# Nebula_1_7OLED.net
KiCad netlist of a schematic drawn in Altium Designer
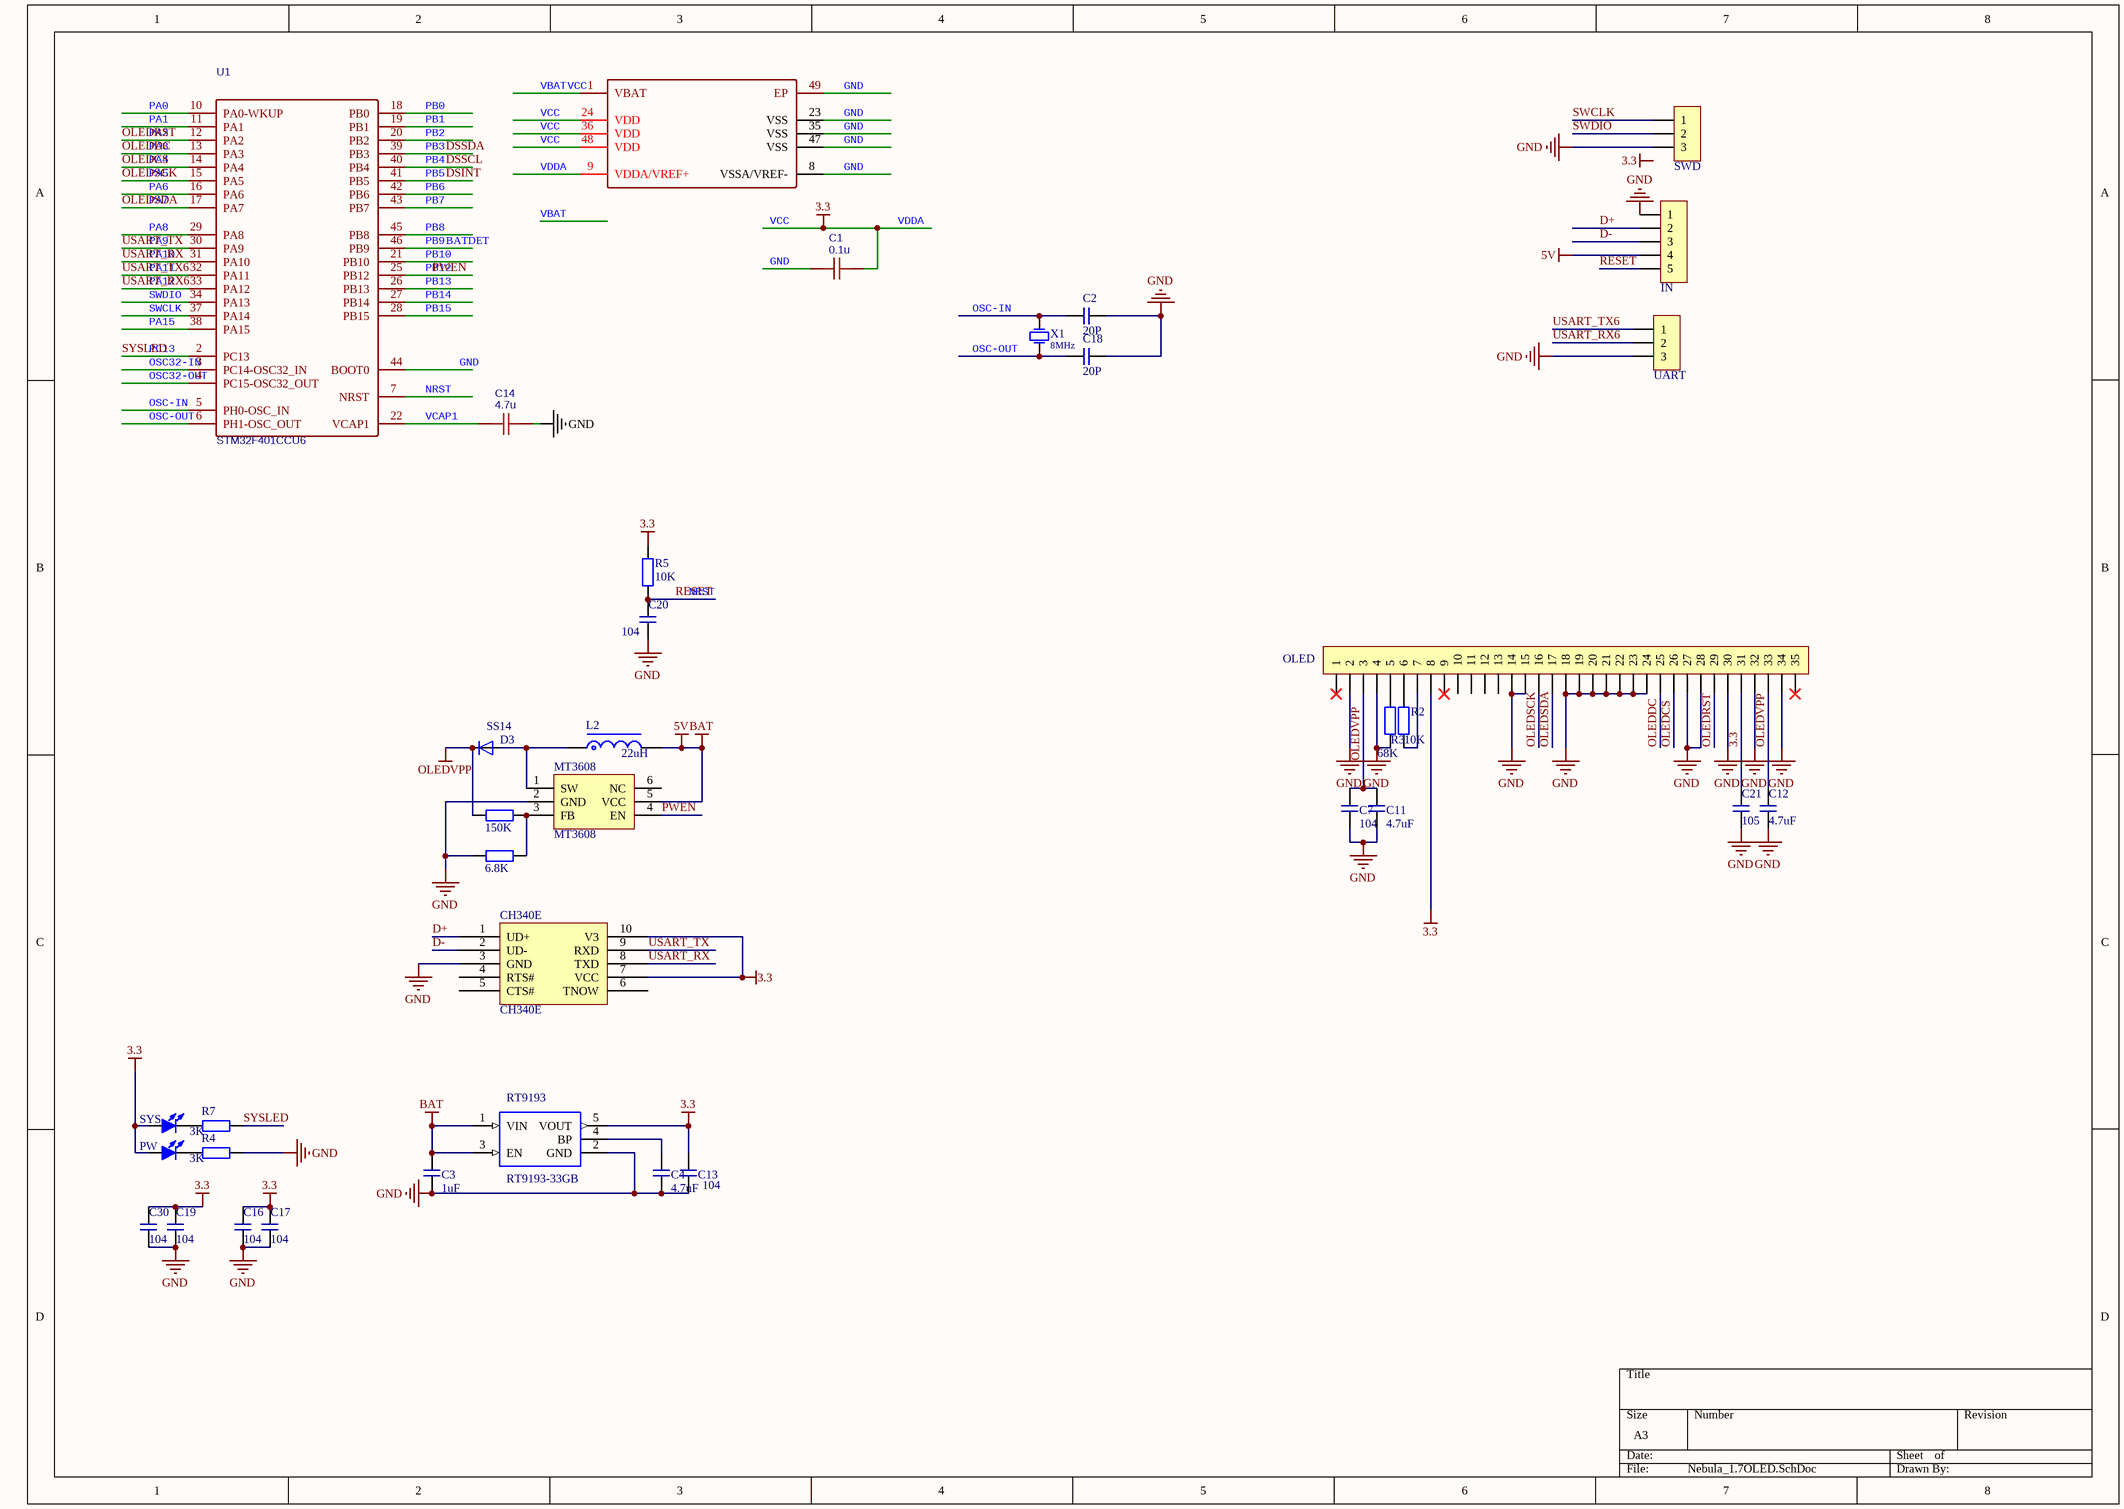
[diagram p0: Nebula_1.7OLED.SchDoc]

(export (version "E")
  (design (tool "Eeschema 10.0.6"))
  (components
    (comp (ref "C1")
      (value "0.1u")
      (footprint "0603C")
      (fields (field (name "CONTRIBUTOR") "LCEDA_Lib"))
      (libsource (lib "altium-import") (part "root_2_0.1u_"))
    )
    (comp (ref "C2") (value "20P") (footprint "0603C") (libsource (lib "Schlib1") (part "电容")))
    (comp (ref "C3") (value "1uF") (footprint "0603C") (libsource (lib "Schlib1") (part "电容")))
    (comp (ref "C4") (value "4.7uF") (footprint "0603C") (libsource (lib "Schlib1") (part "电容")))
    (comp (ref "C7") (value "104") (footprint "0603C") (libsource (lib "Schlib1") (part "电容")))
    (comp (ref "C11") (value "4.7uF") (footprint "0603C") (libsource (lib "Schlib1") (part "电容")))
    (comp (ref "C12") (value "4.7uF") (footprint "0603C") (libsource (lib "Schlib1") (part "电容")))
    (comp (ref "C13") (value "104") (footprint "0603C") (libsource (lib "Schlib1") (part "电容")))
    (comp (ref "C14")
      (value "4.7u")
      (footprint "0603C")
      (fields (field (name "CONTRIBUTOR") "LCEDA_Lib"))
      (libsource (lib "altium-import") (part "root_0_4.7u_"))
    )
    (comp (ref "C16") (value "104") (footprint "0603C") (libsource (lib "Schlib1") (part "电容")))
    (comp (ref "C17") (value "104") (footprint "0603C") (libsource (lib "Schlib1") (part "电容")))
    (comp (ref "C18") (value "20P") (footprint "0603C") (libsource (lib "Schlib1") (part "电容")))
    (comp (ref "C19") (value "104") (footprint "0603C") (libsource (lib "Schlib1") (part "电容")))
    (comp (ref "C20") (value "104") (footprint "0603C") (libsource (lib "Schlib1") (part "电容")))
    (comp (ref "C21") (value "105") (footprint "0603C") (libsource (lib "Schlib1") (part "电容")))
    (comp (ref "C30") (value "104") (footprint "0603C") (libsource (lib "Schlib1") (part "电容")))
    (comp (ref "CH340E") (value "CH340E") (footprint "MSOP10_L") (libsource (lib "CUBE_T1") (part "CH340E")))
    (comp (ref "D3")
      (value "SS14")
      (footprint "SOD323_1N4148WS")
      (description "Diode Switching 75V 0.3A 2-Pin SOD-323 T/R")
      (fields (field (name "MF") "ON Semiconductor") (field (name "MP") "1N4148WS"))
      (libsource (lib "1N4148WS") (part "1N4148WS"))
    )
    (comp (ref "IN")
      (value "HDR-1X5")
      (footprint "ZH1.5-LS-5P")
      (description "5P接插件")
      (fields (field (name "版权归属") "源创客"))
      (libsource (lib "4.3   - 接插件-脚距1.5") (part "Header 5"))
    )
    (comp (ref "L2")
      (value "22uH")
      (footprint "1210-ec")
      (description "功率屏蔽电感")
      (fields (field (name "版权归属") "源创客"))
      (libsource (lib "3.1   - 电阻-电容-电感") (part "L-CDRH"))
    )
    (comp (ref "MT3608")
      (value "MT3608")
      (footprint "SOT23-6N")
      (description "可调升压芯片")
      (fields (field (name "版权归属") "源创客"))
      (libsource (lib "1.3   - 电源类芯片") (part "SX1308"))
    )
    (comp (ref "OLED")
      (value "FPC1.0-35P")
      (footprint "1.69 OLED")
      (description "FPC连接器")
      (fields (field (name "版权归属") "源创客"))
      (libsource (lib "4.14 - FPC连接器") (part "FPC-35P"))
    )
    (comp (ref "PW")
      (value "白色")
      (footprint "0603LED")
      (description "方形LED")
      (fields (field (name "版权归属") "源创客"))
      (libsource (lib "9.1   - LED") (part "LED-F234"))
    )
    (comp (ref "R2")
      (value "10K")
      (footprint "0603R")
      (description "贴片电阻")
      (fields (field (name "版权归属") "源创客"))
      (libsource (lib "3.1   - 电阻-电容-电感") (part "R"))
    )
    (comp (ref "R3")
      (value "68K")
      (footprint "0603R")
      (description "贴片电阻")
      (fields (field (name "版权归属") "源创客"))
      (libsource (lib "3.1   - 电阻-电容-电感") (part "R"))
    )
    (comp (ref "R4")
      (value "3K")
      (footprint "0603R")
      (description "贴片电阻")
      (fields (field (name "版权归属") "源创客"))
      (libsource (lib "3.1   - 电阻-电容-电感") (part "R"))
    )
    (comp (ref "R5")
      (value "10K")
      (footprint "0603R")
      (description "贴片电阻")
      (fields (field (name "版权归属") "源创客"))
      (libsource (lib "3.1   - 电阻-电容-电感") (part "R"))
    )
    (comp (ref "R7")
      (value "3K")
      (footprint "0603R")
      (description "贴片电阻")
      (fields (field (name "版权归属") "源创客"))
      (libsource (lib "3.1   - 电阻-电容-电感") (part "R"))
    )
    (comp (ref "RB")
      (value "150K")
      (footprint "0603R")
      (description "贴片电阻")
      (fields (field (name "版权归属") "源创客"))
      (libsource (lib "3.1   - 电阻-电容-电感") (part "R"))
    )
    (comp (ref "RS")
      (value "6.8K")
      (footprint "0603R")
      (description "贴片电阻")
      (fields (field (name "版权归属") "源创客"))
      (libsource (lib "3.1   - 电阻-电容-电感") (part "R"))
    )
    (comp (ref "RT9193")
      (value "RT9193-33GB")
      (footprint "sot23-5")
      (description "RT9193 Series 300 mA 3.3 V Ultra-Low Noise Ultra-Fast CMOS LDO Regulator-SC-70-5")
      (fields (field (name "MF") "Richtek USA"))
      (libsource (lib "RT9193-33GB") (part "RT9193-33GB"))
    )
    (comp (ref "SWD")
      (value "HDR-1X3")
      (footprint "ZH1.5-LS-3P")
      (description "3P接插件")
      (fields (field (name "版权归属") "源创客"))
      (libsource (lib "4.3   - 接插件-脚距1.5") (part "Header 3"))
    )
    (comp (ref "SYS")
      (value "粉色")
      (footprint "0603LED")
      (description "方形LED")
      (fields (field (name "版权归属") "源创客"))
      (libsource (lib "9.1   - LED") (part "LED-F234"))
    )
    (comp (ref "U1")
      (value "STM32F401CCU6")
      (footprint "QFN48 7X7_N")
      (fields (field (name "BOM_SUPPLIER PART") "C79861") (field (name "SUBPART_NO") "1"))
      (libsource (lib "Galaxy") (part "STM32F401CCU6"))
    )
    (comp (ref "UART")
      (value "HDR-1X3")
      (footprint "ZH1.5-LS-3P")
      (description "3P接插件")
      (fields (field (name "版权归属") "源创客"))
      (libsource (lib "4.3   - 接插件-脚距1.5") (part "Header 3"))
    )
    (comp (ref "X1")
      (value "8MHz")
      (footprint "OSC 5032-2P")
      (description "XTAL,8MHz,±20PPM,12.6*4.5")
      (fields (field (name "Comment") "1.6.1.01.005.001"))
      (libsource (lib "Mark_7") (part "1.6.1.01.005.001"))
    )
  )
  (nets
    (net (code "1") (name "/BATDET") (class "Default")
      (node (ref "U1") (pin "46") (pinfunction "PB9_46") (pintype "passive"))
    )
    (net (code "2") (name "/D+") (class "Default")
      (node (ref "CH340E") (pin "1") (pinfunction "UD+_1") (pintype "passive"))
      (node (ref "IN") (pin "2") (pinfunction "2_2") (pintype "passive"))
    )
    (net (code "3") (name "/D-") (class "Default")
      (node (ref "CH340E") (pin "2") (pinfunction "UD-_2") (pintype "passive"))
      (node (ref "IN") (pin "3") (pinfunction "3_3") (pintype "passive"))
    )
    (net (code "4") (name "/DSINT") (class "Default")
      (node (ref "U1") (pin "41") (pinfunction "PB5_41") (pintype "passive"))
    )
    (net (code "5") (name "/DSSCL") (class "Default")
      (node (ref "U1") (pin "40") (pinfunction "PB4_40") (pintype "passive"))
    )
    (net (code "6") (name "/DSSDA") (class "Default")
      (node (ref "U1") (pin "39") (pinfunction "PB3_39") (pintype "passive"))
    )
    (net (code "7") (name "/NRST") (class "Default")
      (node (ref "C20") (pin "1") (pinfunction "1_1") (pintype "passive"))
      (node (ref "IN") (pin "5") (pinfunction "5_5") (pintype "passive"))
      (node (ref "R5") (pin "2") (pinfunction "2_2") (pintype "passive"))
      (node (ref "U1") (pin "7") (pinfunction "NRST_7") (pintype "passive"))
    )
    (net (code "8") (name "/OLEDCS") (class "Default")
      (node (ref "OLED") (pin "26") (pinfunction "26_26") (pintype "passive"))
      (node (ref "U1") (pin "14") (pinfunction "PA4_14") (pintype "passive"))
    )
    (net (code "9") (name "/OLEDDC") (class "Default")
      (node (ref "OLED") (pin "25") (pinfunction "25_25") (pintype "passive"))
      (node (ref "U1") (pin "13") (pinfunction "PA3_13") (pintype "passive"))
    )
    (net (code "10") (name "/OLEDRST") (class "Default")
      (node (ref "OLED") (pin "29") (pinfunction "29_29") (pintype "passive"))
      (node (ref "U1") (pin "12") (pinfunction "PA2_12") (pintype "passive"))
    )
    (net (code "11") (name "/OLEDSCK") (class "Default")
      (node (ref "OLED") (pin "16") (pinfunction "16_16") (pintype "passive"))
      (node (ref "U1") (pin "15") (pinfunction "PA5_15") (pintype "passive"))
    )
    (net (code "12") (name "/OLEDSDA") (class "Default")
      (node (ref "OLED") (pin "17") (pinfunction "17_17") (pintype "passive"))
      (node (ref "U1") (pin "17") (pinfunction "PA7_17") (pintype "passive"))
    )
    (net (code "13") (name "/OSC-IN") (class "Default")
      (node (ref "C2") (pin "2") (pinfunction "2_2") (pintype "passive"))
      (node (ref "U1") (pin "5") (pinfunction "PH0-OSC_IN_5") (pintype "passive"))
      (node (ref "X1") (pin "1") (pinfunction "OSC1_1") (pintype "passive"))
    )
    (net (code "14") (name "/OSC-OUT") (class "Default")
      (node (ref "C18") (pin "2") (pinfunction "2_2") (pintype "passive"))
      (node (ref "U1") (pin "6") (pinfunction "PH1-OSC_OUT_6") (pintype "passive"))
      (node (ref "X1") (pin "2") (pinfunction "OSC2_2") (pintype "passive"))
    )
    (net (code "15") (name "/OSC32-IN") (class "Default")
      (node (ref "U1") (pin "3") (pinfunction "PC14-OSC32_IN_3") (pintype "passive"))
    )
    (net (code "16") (name "/OSC32-OUT") (class "Default")
      (node (ref "U1") (pin "4") (pinfunction "PC15-OSC32_OUT_4") (pintype "passive"))
    )
    (net (code "17") (name "/PA0") (class "Default")
      (node (ref "U1") (pin "10") (pinfunction "PA0-WKUP_10") (pintype "passive"))
    )
    (net (code "18") (name "/PA1") (class "Default")
      (node (ref "U1") (pin "11") (pinfunction "PA1_11") (pintype "passive"))
    )
    (net (code "19") (name "/PA6") (class "Default")
      (node (ref "U1") (pin "16") (pinfunction "PA6_16") (pintype "passive"))
    )
    (net (code "20") (name "/PA8") (class "Default")
      (node (ref "U1") (pin "29") (pinfunction "PA8_29") (pintype "passive"))
    )
    (net (code "21") (name "/PA9") (class "Default")
      (node (ref "CH340E") (pin "9") (pinfunction "RXD_9") (pintype "passive"))
      (node (ref "U1") (pin "30") (pinfunction "PA9_30") (pintype "passive"))
    )
    (net (code "22") (name "/PA10") (class "Default")
      (node (ref "CH340E") (pin "8") (pinfunction "TXD_8") (pintype "passive"))
      (node (ref "U1") (pin "31") (pinfunction "PA10_31") (pintype "passive"))
    )
    (net (code "23") (name "/PA11") (class "Default")
      (node (ref "U1") (pin "32") (pinfunction "PA11_32") (pintype "passive"))
      (node (ref "UART") (pin "1") (pinfunction "1_1") (pintype "passive"))
    )
    (net (code "24") (name "/PA12") (class "Default")
      (node (ref "U1") (pin "33") (pinfunction "PA12_33") (pintype "passive"))
      (node (ref "UART") (pin "2") (pinfunction "2_2") (pintype "passive"))
    )
    (net (code "25") (name "/PA15") (class "Default")
      (node (ref "U1") (pin "38") (pinfunction "PA15_38") (pintype "passive"))
    )
    (net (code "26") (name "/PB0") (class "Default")
      (node (ref "U1") (pin "18") (pinfunction "PB0_18") (pintype "passive"))
    )
    (net (code "27") (name "/PB1") (class "Default")
      (node (ref "U1") (pin "19") (pinfunction "PB1_19") (pintype "passive"))
    )
    (net (code "28") (name "/PB2") (class "Default")
      (node (ref "U1") (pin "20") (pinfunction "PB2_20") (pintype "passive"))
    )
    (net (code "29") (name "/PB6") (class "Default")
      (node (ref "U1") (pin "42") (pinfunction "PB6_42") (pintype "passive"))
    )
    (net (code "30") (name "/PB7") (class "Default")
      (node (ref "U1") (pin "43") (pinfunction "PB7_43") (pintype "passive"))
    )
    (net (code "31") (name "/PB8") (class "Default")
      (node (ref "U1") (pin "45") (pinfunction "PB8_45") (pintype "passive"))
    )
    (net (code "32") (name "/PB10") (class "Default")
      (node (ref "U1") (pin "21") (pinfunction "PB10_21") (pintype "passive"))
    )
    (net (code "33") (name "/PB12") (class "Default")
      (node (ref "MT3608") (pin "4") (pinfunction "EN_4") (pintype "passive"))
      (node (ref "U1") (pin "25") (pinfunction "PB12_25") (pintype "passive"))
    )
    (net (code "34") (name "/PB13") (class "Default")
      (node (ref "U1") (pin "26") (pinfunction "PB13_26") (pintype "passive"))
    )
    (net (code "35") (name "/PB14") (class "Default")
      (node (ref "U1") (pin "27") (pinfunction "PB14_27") (pintype "passive"))
    )
    (net (code "36") (name "/PB15") (class "Default")
      (node (ref "U1") (pin "28") (pinfunction "PB15_28") (pintype "passive"))
    )
    (net (code "37") (name "/PC13") (class "Default")
      (node (ref "R7") (pin "1") (pinfunction "1_1") (pintype "passive"))
      (node (ref "U1") (pin "2") (pinfunction "PC13_2") (pintype "passive"))
    )
    (net (code "38") (name "/SWCLK") (class "Default")
      (node (ref "SWD") (pin "1") (pinfunction "1_1") (pintype "passive"))
      (node (ref "U1") (pin "37") (pinfunction "PA14_37") (pintype "passive"))
    )
    (net (code "39") (name "/SWDIO") (class "Default")
      (node (ref "SWD") (pin "2") (pinfunction "2_2") (pintype "passive"))
      (node (ref "U1") (pin "34") (pinfunction "PA13_34") (pintype "passive"))
    )
    (net (code "40") (name "/VCAP1") (class "Default")
      (node (ref "C14") (pin "1") (pinfunction "1_1") (pintype "passive"))
      (node (ref "U1") (pin "22") (pinfunction "VCAP1_22") (pintype "passive"))
    )
    (net (code "41") (name "3.3") (class "Default")
      (node (ref "C1") (pin "1") (pinfunction "1_1") (pintype "passive"))
      (node (ref "C13") (pin "2") (pinfunction "2_2") (pintype "passive"))
      (node (ref "C16") (pin "1") (pinfunction "1_1") (pintype "passive"))
      (node (ref "C17") (pin "1") (pinfunction "1_1") (pintype "passive"))
      (node (ref "C19") (pin "1") (pinfunction "1_1") (pintype "passive"))
      (node (ref "C21") (pin "1") (pinfunction "1_1") (pintype "passive"))
      (node (ref "C30") (pin "1") (pinfunction "1_1") (pintype "passive"))
      (node (ref "CH340E") (pin "10") (pinfunction "V3_10") (pintype "passive"))
      (node (ref "CH340E") (pin "7") (pinfunction "VCC_7") (pintype "passive"))
      (node (ref "OLED") (pin "31") (pinfunction "31_31") (pintype "passive"))
      (node (ref "OLED") (pin "8") (pinfunction "8_8") (pintype "passive"))
      (node (ref "PW") (pin "1") (pinfunction "A_1") (pintype "passive"))
      (node (ref "R5") (pin "1") (pinfunction "1_1") (pintype "passive"))
      (node (ref "RT9193") (pin "5") (pinfunction "VOUT_5") (pintype "output"))
      (node (ref "SYS") (pin "1") (pinfunction "A_1") (pintype "passive"))
      (node (ref "U1") (pin "1") (pinfunction "VBAT_1") (pintype "passive"))
      (node (ref "U1") (pin "24") (pinfunction "VDD_24") (pintype "passive"))
      (node (ref "U1") (pin "36") (pinfunction "VDD_36") (pintype "passive"))
      (node (ref "U1") (pin "48") (pinfunction "VDD_48") (pintype "passive"))
      (node (ref "U1") (pin "9") (pinfunction "VDDA/VREF+_9") (pintype "passive"))
    )
    (net (code "42") (name "5V") (class "Default")
      (node (ref "C3") (pin "2") (pinfunction "2_2") (pintype "passive"))
      (node (ref "IN") (pin "4") (pinfunction "4_4") (pintype "passive"))
      (node (ref "L2") (pin "2") (pinfunction "2_2") (pintype "passive"))
      (node (ref "MT3608") (pin "5") (pinfunction "VCC_5") (pintype "passive"))
      (node (ref "RT9193") (pin "1") (pinfunction "VIN_1") (pintype "input"))
      (node (ref "RT9193") (pin "3") (pinfunction "EN_3") (pintype "input"))
    )
    (net (code "43") (name "GND") (class "Default")
      (node (ref "C1") (pin "2") (pinfunction "2_2") (pintype "passive"))
      (node (ref "C11") (pin "2") (pinfunction "2_2") (pintype "passive"))
      (node (ref "C12") (pin "2") (pinfunction "2_2") (pintype "passive"))
      (node (ref "C13") (pin "1") (pinfunction "1_1") (pintype "passive"))
      (node (ref "C14") (pin "2") (pinfunction "2_2") (pintype "passive"))
      (node (ref "C16") (pin "2") (pinfunction "2_2") (pintype "passive"))
      (node (ref "C17") (pin "2") (pinfunction "2_2") (pintype "passive"))
      (node (ref "C18") (pin "1") (pinfunction "1_1") (pintype "passive"))
      (node (ref "C19") (pin "2") (pinfunction "2_2") (pintype "passive"))
      (node (ref "C2") (pin "1") (pinfunction "1_1") (pintype "passive"))
      (node (ref "C20") (pin "2") (pinfunction "2_2") (pintype "passive"))
      (node (ref "C21") (pin "2") (pinfunction "2_2") (pintype "passive"))
      (node (ref "C3") (pin "1") (pinfunction "1_1") (pintype "passive"))
      (node (ref "C30") (pin "2") (pinfunction "2_2") (pintype "passive"))
      (node (ref "C4") (pin "1") (pinfunction "1_1") (pintype "passive"))
      (node (ref "C7") (pin "2") (pinfunction "2_2") (pintype "passive"))
      (node (ref "CH340E") (pin "3") (pinfunction "GND_3") (pintype "passive"))
      (node (ref "IN") (pin "1") (pinfunction "1_1") (pintype "passive"))
      (node (ref "MT3608") (pin "2") (pinfunction "GND_2") (pintype "passive"))
      (node (ref "OLED") (pin "14") (pinfunction "14_14") (pintype "passive"))
      (node (ref "OLED") (pin "15") (pinfunction "15_15") (pintype "passive"))
      (node (ref "OLED") (pin "18") (pinfunction "18_18") (pintype "passive"))
      (node (ref "OLED") (pin "19") (pinfunction "19_19") (pintype "passive"))
      (node (ref "OLED") (pin "2") (pinfunction "2_2") (pintype "passive"))
      (node (ref "OLED") (pin "20") (pinfunction "20_20") (pintype "passive"))
      (node (ref "OLED") (pin "21") (pinfunction "21_21") (pintype "passive"))
      (node (ref "OLED") (pin "22") (pinfunction "22_22") (pintype "passive"))
      (node (ref "OLED") (pin "23") (pinfunction "23_23") (pintype "passive"))
      (node (ref "OLED") (pin "24") (pinfunction "24_24") (pintype "passive"))
      (node (ref "OLED") (pin "27") (pinfunction "27_27") (pintype "passive"))
      (node (ref "OLED") (pin "28") (pinfunction "28_28") (pintype "passive"))
      (node (ref "OLED") (pin "30") (pinfunction "30_30") (pintype "passive"))
      (node (ref "OLED") (pin "32") (pinfunction "32_32") (pintype "passive"))
      (node (ref "OLED") (pin "34") (pinfunction "34_34") (pintype "passive"))
      (node (ref "OLED") (pin "4") (pinfunction "4_4") (pintype "passive"))
      (node (ref "R3") (pin "1") (pinfunction "1_1") (pintype "passive"))
      (node (ref "R4") (pin "1") (pinfunction "1_1") (pintype "passive"))
      (node (ref "RS") (pin "1") (pinfunction "1_1") (pintype "passive"))
      (node (ref "RT9193") (pin "2") (pinfunction "GND_2") (pintype "power_in"))
      (node (ref "SWD") (pin "3") (pinfunction "3_3") (pintype "passive"))
      (node (ref "U1") (pin "23") (pinfunction "VSS_23") (pintype "passive"))
      (node (ref "U1") (pin "35") (pinfunction "VSS_35") (pintype "passive"))
      (node (ref "U1") (pin "44") (pinfunction "BOOT0_44") (pintype "passive"))
      (node (ref "U1") (pin "47") (pinfunction "VSS_47") (pintype "passive"))
      (node (ref "U1") (pin "49") (pinfunction "EP_49") (pintype "passive"))
      (node (ref "U1") (pin "8") (pinfunction "VSSA/VREF-_8") (pintype "passive"))
      (node (ref "UART") (pin "3") (pinfunction "3_3") (pintype "passive"))
    )
    (net (code "44") (name "Net-(MT3608-FB)") (class "Default")
      (node (ref "MT3608") (pin "3") (pinfunction "FB_3") (pintype "passive"))
      (node (ref "RB") (pin "2") (pinfunction "2_2") (pintype "passive"))
      (node (ref "RS") (pin "2") (pinfunction "2_2") (pintype "passive"))
    )
    (net (code "45") (name "Net-(MT3608-SW)") (class "Default")
      (node (ref "D3") (pin "A") (pinfunction "A_A") (pintype "passive"))
      (node (ref "L2") (pin "1") (pinfunction "1_1") (pintype "passive"))
      (node (ref "MT3608") (pin "1") (pinfunction "SW_1") (pintype "passive"))
    )
    (net (code "46") (name "Net-(OLED-Pad5)") (class "Default")
      (node (ref "OLED") (pin "5") (pinfunction "5_5") (pintype "passive"))
      (node (ref "R3") (pin "2") (pinfunction "2_2") (pintype "passive"))
    )
    (net (code "47") (name "Net-(OLED-Pad6)") (class "Default")
      (node (ref "OLED") (pin "6") (pinfunction "6_6") (pintype "passive"))
      (node (ref "R2") (pin "2") (pinfunction "2_2") (pintype "passive"))
    )
    (net (code "48") (name "Net-(OLED-Pad7)") (class "Default")
      (node (ref "OLED") (pin "7") (pinfunction "7_7") (pintype "passive"))
      (node (ref "R2") (pin "1") (pinfunction "1_1") (pintype "passive"))
    )
    (net (code "49") (name "Net-(PW-K)") (class "Default")
      (node (ref "PW") (pin "2") (pinfunction "K_2") (pintype "passive"))
      (node (ref "R4") (pin "2") (pinfunction "2_2") (pintype "passive"))
    )
    (net (code "50") (name "Net-(RT9193-BP)") (class "Default")
      (node (ref "C4") (pin "2") (pinfunction "2_2") (pintype "passive"))
      (node (ref "RT9193") (pin "4") (pinfunction "BP_4") (pintype "passive"))
    )
    (net (code "51") (name "Net-(SYS-K)") (class "Default")
      (node (ref "R7") (pin "2") (pinfunction "2_2") (pintype "passive"))
      (node (ref "SYS") (pin "2") (pinfunction "K_2") (pintype "passive"))
    )
    (net (code "52") (name "OLEDVPP") (class "Default")
      (node (ref "C11") (pin "1") (pinfunction "1_1") (pintype "passive"))
      (node (ref "C12") (pin "1") (pinfunction "1_1") (pintype "passive"))
      (node (ref "C7") (pin "1") (pinfunction "1_1") (pintype "passive"))
      (node (ref "D3") (pin "C") (pinfunction "C_C") (pintype "passive"))
      (node (ref "OLED") (pin "3") (pinfunction "3_3") (pintype "passive"))
      (node (ref "OLED") (pin "33") (pinfunction "33_33") (pintype "passive"))
      (node (ref "RB") (pin "1") (pinfunction "1_1") (pintype "passive"))
    )
    (net (code "53") (name "unconnected-(CH340E-CTS#-Pad5)") (class "Default")
      (node (ref "CH340E") (pin "5") (pinfunction "CTS#_5") (pintype "passive"))
    )
    (net (code "54") (name "unconnected-(CH340E-RTS#-Pad4)") (class "Default")
      (node (ref "CH340E") (pin "4") (pinfunction "RTS#_4") (pintype "passive"))
    )
    (net (code "55") (name "unconnected-(CH340E-TNOW-Pad6)") (class "Default")
      (node (ref "CH340E") (pin "6") (pinfunction "TNOW_6") (pintype "passive"))
    )
    (net (code "56") (name "unconnected-(MT3608-NC-Pad6)") (class "Default")
      (node (ref "MT3608") (pin "6") (pinfunction "NC_6") (pintype "passive"))
    )
    (net (code "57") (name "unconnected-(OLED-Pad1)") (class "Default")
      (node (ref "OLED") (pin "1") (pinfunction "1_1") (pintype "passive+no_connect"))
    )
    (net (code "58") (name "unconnected-(OLED-Pad9)") (class "Default")
      (node (ref "OLED") (pin "9") (pinfunction "9_9") (pintype "passive+no_connect"))
    )
    (net (code "59") (name "unconnected-(OLED-Pad10)") (class "Default")
      (node (ref "OLED") (pin "10") (pinfunction "10_10") (pintype "passive"))
    )
    (net (code "60") (name "unconnected-(OLED-Pad11)") (class "Default")
      (node (ref "OLED") (pin "11") (pinfunction "11_11") (pintype "passive"))
    )
    (net (code "61") (name "unconnected-(OLED-Pad12)") (class "Default")
      (node (ref "OLED") (pin "12") (pinfunction "12_12") (pintype "passive"))
    )
    (net (code "62") (name "unconnected-(OLED-Pad13)") (class "Default")
      (node (ref "OLED") (pin "13") (pinfunction "13_13") (pintype "passive"))
    )
    (net (code "63") (name "unconnected-(OLED-Pad35)") (class "Default")
      (node (ref "OLED") (pin "35") (pinfunction "35_35") (pintype "passive+no_connect"))
    )
  )
)
